# StereoscopicPi.net
KiCad netlist of a schematic drawn in Altium Designer
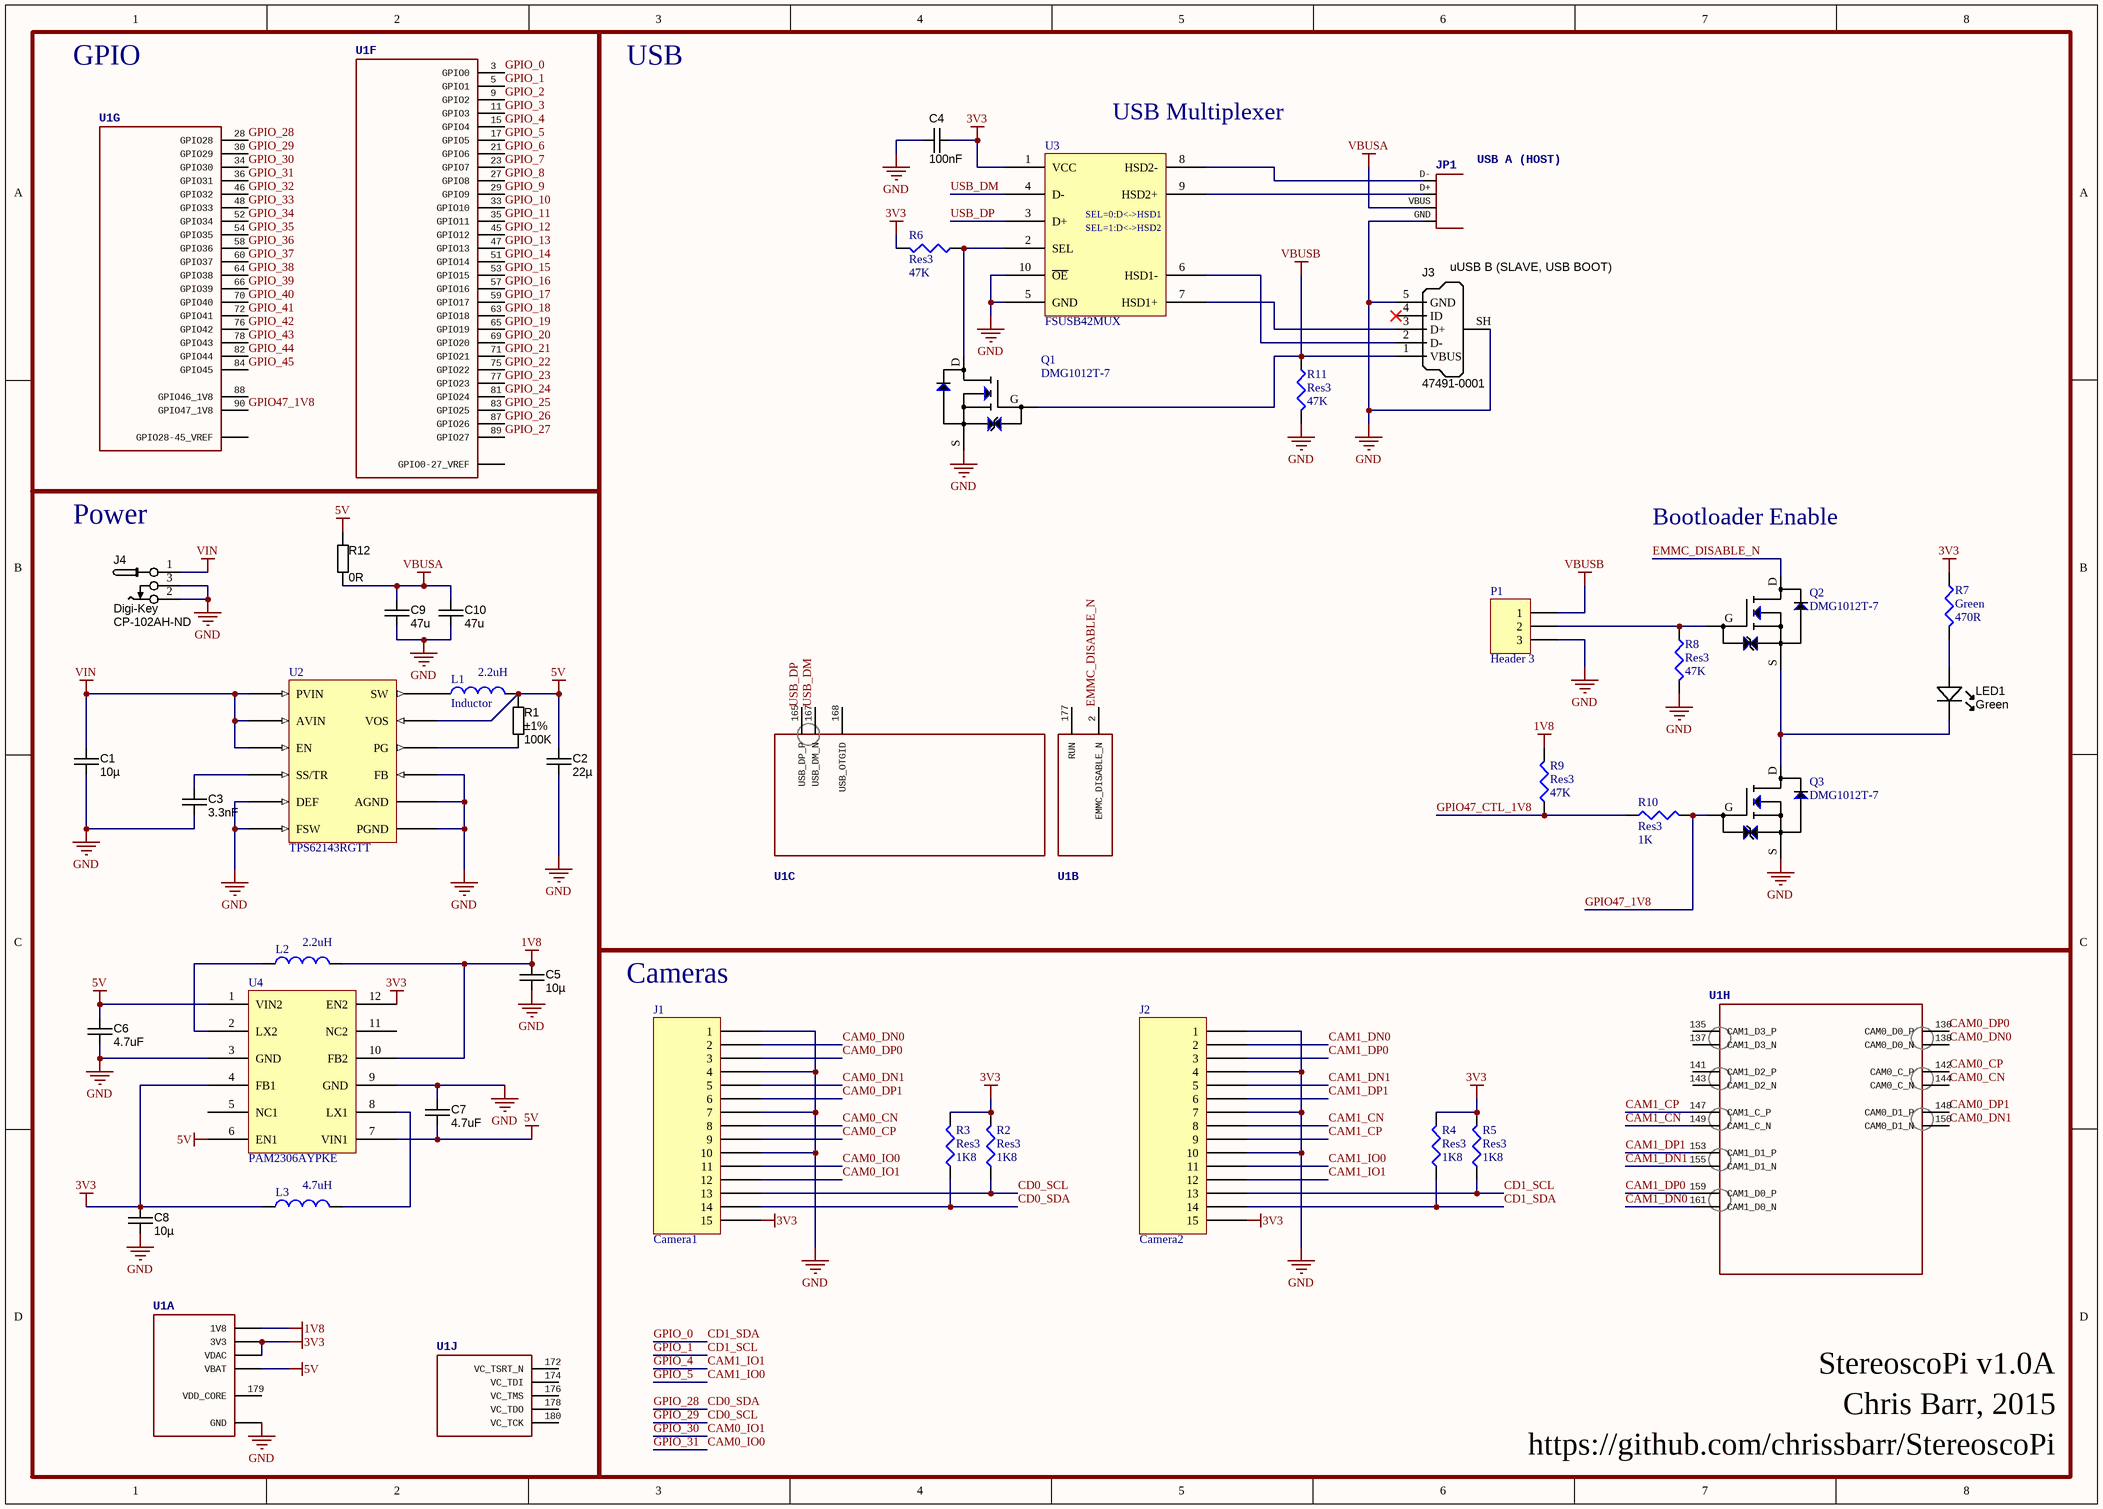
[diagram p0: StereoscopicPi.SchDoc]

(export (version "E")
  (design (tool "Eeschema 10.0.6"))
  (components
    (comp (ref "C1")
      (value "10µ")
      (footprint "CAPC3225X220N")
      (description "Capacitor SMD Cer 10uF 20% 16V X5R 1210")
      (fields (field (name "TOLERANCE") "±20%"))
      (libsource (lib "PBL - Capacitors") (part "CAPC_10u_1210_50V"))
    )
    (comp (ref "C2")
      (value "22µ")
      (footprint "CAPC3225X220N")
      (description "Capacitor SMD Cer 22uF 20% 6.3V X5R 1210")
      (fields (field (name "TOLERANCE") "±20%") (field (name "Comment") "approved sub OK"))
      (libsource (lib "PBL - Capacitors") (part "CAPC_22u_1210_6V3_X5R"))
    )
    (comp (ref "C3")
      (value "3.3nF")
      (footprint "CAPC1608X90N")
      (description "Capacitor SMD Cer 10nF 10% 50V X7R 0603")
      (fields (field (name "TOLERANCE") "±10%") (field (name "Comment") "Kemet C0603C332J3RACTU"))
      (libsource (lib "PBL - Capacitors") (part "CAPC_10n_0603_X7R_50V_10%"))
    )
    (comp (ref "C4")
      (value "100nF")
      (footprint "CAPC1608X90N")
      (description "Capacitor SMD Cer 10nF 10% 50V X7R 0603")
      (fields (field (name "TOLERANCE") "±10%"))
      (libsource (lib "PBL - Capacitors") (part "CAPC_10n_0603_X7R_50V_10%"))
    )
    (comp (ref "C5")
      (value "10µ")
      (footprint "CAPC3225X220N")
      (description "Capacitor SMD Cer 10uF 20% 16V X5R 1210")
      (fields (field (name "TOLERANCE") "±20%"))
      (libsource (lib "PBL - Capacitors") (part "CAPC_10u_1210_50V"))
    )
    (comp (ref "C6")
      (value "4.7uF")
      (footprint "CAPC2012X135N")
      (description "Capacitor SMD Cer 4.7uF 10% 16V X5R 0805")
      (fields (field (name "TOLERANCE") "±10%") (field (name "Comment") "approved sub OK"))
      (libsource (lib "PBL - Capacitors") (part "CAPC_4u7_0805"))
    )
    (comp (ref "C7")
      (value "4.7uF")
      (footprint "CAPC2012X135N")
      (description "Capacitor SMD Cer 4.7uF 10% 16V X5R 0805")
      (fields (field (name "TOLERANCE") "±10%") (field (name "Comment") "approved sub OK"))
      (libsource (lib "PBL - Capacitors") (part "CAPC_4u7_0805"))
    )
    (comp (ref "C8")
      (value "10µ")
      (footprint "CAPC3225X220N")
      (description "Capacitor SMD Cer 10uF 20% 16V X5R 1210")
      (fields (field (name "TOLERANCE") "±20%"))
      (libsource (lib "PBL - Capacitors") (part "CAPC_10u_1210_50V"))
    )
    (comp (ref "C9")
      (value "47u")
      (footprint "CAPC3225X220N")
      (description "Capacitor SMD Cer 47uF 10% 10V 1210")
      (fields (field (name "TOLERANCE") "±10%"))
      (libsource (lib "PBL - Capacitors") (part "CAPC_47u_1210_10V_X5R_10%"))
    )
    (comp (ref "C10")
      (value "47u")
      (footprint "CAPC3225X220N")
      (description "Capacitor SMD Cer 47uF 10% 10V 1210")
      (fields (field (name "TOLERANCE") "±10%"))
      (libsource (lib "PBL - Capacitors") (part "CAPC_47u_1210_10V_X5R_10%"))
    )
    (comp (ref "J1")
      (value "Camera1")
      (footprint "SFW15R-2STE1LF")
      (libsource (lib "Schlib1") (part "SFW15R-2STE1LF"))
    )
    (comp (ref "J2")
      (value "Camera2")
      (footprint "SFW15R-2STE1LF")
      (libsource (lib "Schlib1") (part "SFW15R-2STE1LF"))
    )
    (comp (ref "J3")
      (value "uUSB B (SLAVE, USB BOOT)")
      (footprint "USB_Micro-B_Molex_SMD")
      (description "Connector SMD USB Micro Type B middle mount")
      (fields (field (name "MANUFACTURER PART NUMBER 1") "47491-0001"))
      (libsource (lib "PBL - Connectors") (part "USB_Micro_TypeB"))
    )
    (comp (ref "J4")
      (value "CONN_PWR_JACK_2.1x5.5mm")
      (footprint "CONN_PWR_JACK_2.1x5.5mm")
      (description "Power Connector, THT, 2.1mm ID, 5.5mm OD")
      (fields (field (name "SUPPLIER 1") "Digi-Key") (field (name "SUPPLIER PART NUMBER 1") "CP-102AH-ND"))
      (libsource (lib "PBL - Connectors") (part "CONN_PWR_JACK_2.1x5.5mm"))
    )
    (comp (ref "JP1")
      (value "USB A (HOST)")
      (footprint "USB-A-S-NOSILK-FEMALE")
      (libsource (lib "SparkFun-Connectors") (part "USB-A-SMD"))
    )
    (comp (ref "L1")
      (value "Inductor")
      (footprint "IHLP-1212BZ-11")
      (fields (field (name "ALTIUM_VALUE") "2.2uH") (field (name "PUBLISHER") "Altium Limited"))
      (libsource (lib "Miscellaneous Devices") (part "Inductor"))
    )
    (comp (ref "L2")
      (value "2.2uH")
      (footprint "IHLP-1212BZ-11")
      (description "Inductor")
      (fields (field (name "Comment") "IHLP1212BZER2R2M11") (field (name "PUBLISHER") "Altium Limited"))
      (libsource (lib "Miscellaneous Devices") (part "Inductor"))
    )
    (comp (ref "L3")
      (value "4.7uH")
      (footprint "IHLP-2020CZ-11")
      (description "Inductor")
      (fields (field (name "Comment") "IHLP2020CZER4R7M11") (field (name "PUBLISHER") "Altium Limited"))
      (libsource (lib "Miscellaneous Devices") (part "Inductor"))
    )
    (comp (ref "LED1")
      (value "Green")
      (footprint "LED-0603-GREEN")
      (description "LED 0603 SMD Green 570nm 50mcd 20mA")
      (libsource (lib "PBL - Light Sources") (part "LED_SMD_Green_0603_570nm"))
    )
    (comp (ref "P1")
      (value "Header 3")
      (footprint "HDR1X3")
      (description "Header, 3-Pin")
      (fields (field (name "PUBLISHER") "Altium Limited"))
      (libsource (lib "Miscellaneous Connectors") (part "Header 3"))
    )
    (comp (ref "Q1")
      (value "DMG1012T-7")
      (footprint "DMG1012T-7")
      (libsource (lib "Schlib1") (part "DMG1012T-7"))
    )
    (comp (ref "Q2")
      (value "DMG1012T-7")
      (footprint "DMG1012T-7")
      (libsource (lib "Schlib1") (part "DMG1012T-7"))
    )
    (comp (ref "Q3")
      (value "DMG1012T-7")
      (footprint "DMG1012T-7")
      (libsource (lib "Schlib1") (part "DMG1012T-7"))
    )
    (comp (ref "R1")
      (value "100K")
      (footprint "RESC1608X55N")
      (description "Resistor SMD chip 100k Ohm 0.1W 1% 0603")
      (fields (field (name "TOLERANCE") "±1%") (field (name "Comment") "Thick Film"))
      (libsource (lib "PBL - Resistors") (part "RES_100K_0603_1%"))
    )
    (comp (ref "R2")
      (value "Res3")
      (footprint "J1-0603")
      (description "Resistor")
      (fields (field (name "ALTIUM_VALUE") "1K8") (field (name "PUBLISHER") "Altium Limited"))
      (libsource (lib "Miscellaneous Devices") (part "Res3"))
    )
    (comp (ref "R3")
      (value "Res3")
      (footprint "J1-0603")
      (description "Resistor")
      (fields (field (name "ALTIUM_VALUE") "1K8") (field (name "PUBLISHER") "Altium Limited"))
      (libsource (lib "Miscellaneous Devices") (part "Res3"))
    )
    (comp (ref "R4")
      (value "Res3")
      (footprint "J1-0603")
      (description "Resistor")
      (fields (field (name "ALTIUM_VALUE") "1K8") (field (name "PUBLISHER") "Altium Limited"))
      (libsource (lib "Miscellaneous Devices") (part "Res3"))
    )
    (comp (ref "R5")
      (value "Res3")
      (footprint "J1-0603")
      (description "Resistor")
      (fields (field (name "ALTIUM_VALUE") "1K8") (field (name "PUBLISHER") "Altium Limited"))
      (libsource (lib "Miscellaneous Devices") (part "Res3"))
    )
    (comp (ref "R6")
      (value "Res3")
      (footprint "J1-0603")
      (description "Resistor")
      (fields (field (name "ALTIUM_VALUE") "47K") (field (name "PUBLISHER") "Altium Limited"))
      (libsource (lib "Miscellaneous Devices") (part "Res3"))
    )
    (comp (ref "R7")
      (value "Green")
      (footprint "J1-0603")
      (description "Resistor")
      (fields (field (name "ALTIUM_VALUE") "470R") (field (name "PUBLISHER") "Altium Limited"))
      (libsource (lib "Miscellaneous Devices") (part "Res3"))
    )
    (comp (ref "R8")
      (value "Res3")
      (footprint "J1-0603")
      (description "Resistor")
      (fields (field (name "ALTIUM_VALUE") "47K") (field (name "PUBLISHER") "Altium Limited"))
      (libsource (lib "Miscellaneous Devices") (part "Res3"))
    )
    (comp (ref "R9")
      (value "Res3")
      (footprint "J1-0603")
      (description "Resistor")
      (fields (field (name "ALTIUM_VALUE") "47K") (field (name "PUBLISHER") "Altium Limited"))
      (libsource (lib "Miscellaneous Devices") (part "Res3"))
    )
    (comp (ref "R10")
      (value "Res3")
      (footprint "J1-0603")
      (description "Resistor")
      (fields (field (name "ALTIUM_VALUE") "1K") (field (name "PUBLISHER") "Altium Limited"))
      (libsource (lib "Miscellaneous Devices") (part "Res3"))
    )
    (comp (ref "R11")
      (value "Res3")
      (footprint "J1-0603")
      (description "Resistor")
      (fields (field (name "ALTIUM_VALUE") "47K") (field (name "PUBLISHER") "Altium Limited"))
      (libsource (lib "Miscellaneous Devices") (part "Res3"))
    )
    (comp (ref "R12")
      (value "0R")
      (footprint "RESC1608X55N")
      (description "Resistor SMD chip 100k Ohm 0.1W 1% 0603")
      (fields (field (name "TOLERANCE") "±1%") (field (name "Comment") "Thick Film"))
      (libsource (lib "PBL - Resistors") (part "RES_100K_0603_1%"))
    )
    (comp (ref "U1")
      (value "Raspberry Pi Compute Module As anounced in this blog post  http://www.raspberrypi.org/raspberry-pi-compute-module-new-product/  Based on infomation from this schematic http://www.raspberrypi.org/wp-content/uploads/2014/04/RPI-CM-V1_1-SCHEMATIC.pdf  Footprint is unproven and no matching part confimed as of yet")
      (footprint "1-1376408-4")
      (libsource (lib "Ciseco Pi Compute Module") (part "RASPBERRY_PI_CM-1-1376408-4"))
    )
    (comp (ref "U2")
      (value "TPS62143RGTT")
      (footprint "QFN50P300X300X100_HS-17M")
      (libsource (lib "Schlib1") (part "TPS62143 5V 2A LDO SMPS Buck"))
    )
    (comp (ref "U3")
      (value "FSUSB42MUX")
      (footprint "FSUSB42MUX")
      (libsource (lib "Schlib1") (part "FSUSB42MUX"))
    )
    (comp (ref "U4")
      (value "PAM2306AYPKE")
      (footprint "PAM2306")
      (libsource (lib "Schlib1") (part "PAM2306"))
    )
  )
  (nets
    (net (code "1") (name "/CAM0_CN") (class "Default")
      (node (ref "J1") (pin "8") (pinfunction "8_8") (pintype "passive"))
      (node (ref "U1") (pin "144") (pinfunction "CAM0_C_N_144") (pintype "passive"))
    )
    (net (code "2") (name "/CAM0_CP") (class "Default")
      (node (ref "J1") (pin "9") (pinfunction "9_9") (pintype "passive"))
      (node (ref "U1") (pin "142") (pinfunction "CAM0_C_P_142") (pintype "passive"))
    )
    (net (code "3") (name "/CAM0_DN0") (class "Default")
      (node (ref "J1") (pin "2") (pinfunction "2_2") (pintype "passive"))
      (node (ref "U1") (pin "138") (pinfunction "CAM0_D0_N_138") (pintype "passive"))
    )
    (net (code "4") (name "/CAM0_DN1") (class "Default")
      (node (ref "J1") (pin "5") (pinfunction "5_5") (pintype "passive"))
      (node (ref "U1") (pin "150") (pinfunction "CAM0_D1_N_150") (pintype "passive"))
    )
    (net (code "5") (name "/CAM0_DP0") (class "Default")
      (node (ref "J1") (pin "3") (pinfunction "3_3") (pintype "passive"))
      (node (ref "U1") (pin "136") (pinfunction "CAM0_D0_P_136") (pintype "passive"))
    )
    (net (code "6") (name "/CAM0_DP1") (class "Default")
      (node (ref "J1") (pin "6") (pinfunction "6_6") (pintype "passive"))
      (node (ref "U1") (pin "148") (pinfunction "CAM0_D1_P_148") (pintype "passive"))
    )
    (net (code "7") (name "/CAM0_IO0") (class "Default")
      (node (ref "J1") (pin "11") (pinfunction "11_11") (pintype "passive"))
      (node (ref "U1") (pin "36") (pinfunction "GPIO31_36") (pintype "passive"))
    )
    (net (code "8") (name "/CAM0_IO1") (class "Default")
      (node (ref "J1") (pin "12") (pinfunction "12_12") (pintype "passive"))
      (node (ref "U1") (pin "34") (pinfunction "GPIO30_34") (pintype "passive"))
    )
    (net (code "9") (name "/CAM1_CN") (class "Default")
      (node (ref "J2") (pin "8") (pinfunction "8_8") (pintype "passive"))
      (node (ref "U1") (pin "149") (pinfunction "CAM1_C_N_149") (pintype "passive"))
    )
    (net (code "10") (name "/CAM1_CP") (class "Default")
      (node (ref "J2") (pin "9") (pinfunction "9_9") (pintype "passive"))
      (node (ref "U1") (pin "147") (pinfunction "CAM1_C_P_147") (pintype "passive"))
    )
    (net (code "11") (name "/CAM1_DN0") (class "Default")
      (node (ref "J2") (pin "2") (pinfunction "2_2") (pintype "passive"))
      (node (ref "U1") (pin "161") (pinfunction "CAM1_D0_N_161") (pintype "passive"))
    )
    (net (code "12") (name "/CAM1_DN1") (class "Default")
      (node (ref "J2") (pin "5") (pinfunction "5_5") (pintype "passive"))
      (node (ref "U1") (pin "155") (pinfunction "CAM1_D1_N_155") (pintype "passive"))
    )
    (net (code "13") (name "/CAM1_DP0") (class "Default")
      (node (ref "J2") (pin "3") (pinfunction "3_3") (pintype "passive"))
      (node (ref "U1") (pin "159") (pinfunction "CAM1_D0_P_159") (pintype "passive"))
    )
    (net (code "14") (name "/CAM1_DP1") (class "Default")
      (node (ref "J2") (pin "6") (pinfunction "6_6") (pintype "passive"))
      (node (ref "U1") (pin "153") (pinfunction "CAM1_D1_P_153") (pintype "passive"))
    )
    (net (code "15") (name "/CAM1_IO0") (class "Default")
      (node (ref "J2") (pin "11") (pinfunction "11_11") (pintype "passive"))
      (node (ref "U1") (pin "17") (pinfunction "GPIO5_17") (pintype "passive"))
    )
    (net (code "16") (name "/CAM1_IO1") (class "Default")
      (node (ref "J2") (pin "12") (pinfunction "12_12") (pintype "passive"))
      (node (ref "U1") (pin "15") (pinfunction "GPIO4_15") (pintype "passive"))
    )
    (net (code "17") (name "/CD0_SCL") (class "Default")
      (node (ref "J1") (pin "13") (pinfunction "13_13") (pintype "passive"))
      (node (ref "R2") (pin "1") (pinfunction "1_1") (pintype "passive"))
      (node (ref "U1") (pin "30") (pinfunction "GPIO29_30") (pintype "passive"))
    )
    (net (code "18") (name "/CD0_SDA") (class "Default")
      (node (ref "J1") (pin "14") (pinfunction "14_14") (pintype "passive"))
      (node (ref "R3") (pin "1") (pinfunction "1_1") (pintype "passive"))
      (node (ref "U1") (pin "28") (pinfunction "GPIO28_28") (pintype "passive"))
    )
    (net (code "19") (name "/CD1_SCL") (class "Default")
      (node (ref "J2") (pin "13") (pinfunction "13_13") (pintype "passive"))
      (node (ref "R5") (pin "1") (pinfunction "1_1") (pintype "passive"))
      (node (ref "U1") (pin "5") (pinfunction "GPIO1_5") (pintype "passive"))
    )
    (net (code "20") (name "/CD1_SDA") (class "Default")
      (node (ref "J2") (pin "14") (pinfunction "14_14") (pintype "passive"))
      (node (ref "R4") (pin "1") (pinfunction "1_1") (pintype "passive"))
      (node (ref "U1") (pin "3") (pinfunction "GPIO0_3") (pintype "passive"))
    )
    (net (code "21") (name "/EMMC_DISABLE_N") (class "Default")
      (node (ref "Q2") (pin "D") (pinfunction "D_D") (pintype "passive"))
      (node (ref "U1") (pin "2") (pinfunction "EMMC_DISABLE_N_2") (pintype "passive"))
    )
    (net (code "22") (name "/GPIO47_1V8") (class "Default")
      (node (ref "Q3") (pin "G") (pinfunction "G_G") (pintype "passive"))
      (node (ref "R10") (pin "2") (pinfunction "2_2") (pintype "passive"))
      (node (ref "U1") (pin "90") (pinfunction "GPIO47_1V8_90") (pintype "passive"))
    )
    (net (code "23") (name "/GPIO47_CTL_1V8") (class "Default")
      (node (ref "R10") (pin "1") (pinfunction "1_1") (pintype "passive"))
      (node (ref "R9") (pin "1") (pinfunction "1_1") (pintype "passive"))
    )
    (net (code "24") (name "/GPIO_2") (class "Default")
      (node (ref "U1") (pin "9") (pinfunction "GPIO2_9") (pintype "passive"))
    )
    (net (code "25") (name "/GPIO_3") (class "Default")
      (node (ref "U1") (pin "11") (pinfunction "GPIO3_11") (pintype "passive"))
    )
    (net (code "26") (name "/GPIO_6") (class "Default")
      (node (ref "U1") (pin "21") (pinfunction "GPIO6_21") (pintype "passive"))
    )
    (net (code "27") (name "/GPIO_7") (class "Default")
      (node (ref "U1") (pin "23") (pinfunction "GPIO7_23") (pintype "passive"))
    )
    (net (code "28") (name "/GPIO_8") (class "Default")
      (node (ref "U1") (pin "27") (pinfunction "GPIO8_27") (pintype "passive"))
    )
    (net (code "29") (name "/GPIO_9") (class "Default")
      (node (ref "U1") (pin "29") (pinfunction "GPIO9_29") (pintype "passive"))
    )
    (net (code "30") (name "/GPIO_10") (class "Default")
      (node (ref "U1") (pin "33") (pinfunction "GPIO10_33") (pintype "passive"))
    )
    (net (code "31") (name "/GPIO_11") (class "Default")
      (node (ref "U1") (pin "35") (pinfunction "GPIO11_35") (pintype "passive"))
    )
    (net (code "32") (name "/GPIO_12") (class "Default")
      (node (ref "U1") (pin "45") (pinfunction "GPIO12_45") (pintype "passive"))
    )
    (net (code "33") (name "/GPIO_13") (class "Default")
      (node (ref "U1") (pin "47") (pinfunction "GPIO13_47") (pintype "passive"))
    )
    (net (code "34") (name "/GPIO_14") (class "Default")
      (node (ref "U1") (pin "51") (pinfunction "GPIO14_51") (pintype "passive"))
    )
    (net (code "35") (name "/GPIO_15") (class "Default")
      (node (ref "U1") (pin "53") (pinfunction "GPIO15_53") (pintype "passive"))
    )
    (net (code "36") (name "/GPIO_16") (class "Default")
      (node (ref "U1") (pin "57") (pinfunction "GPIO16_57") (pintype "passive"))
    )
    (net (code "37") (name "/GPIO_17") (class "Default")
      (node (ref "U1") (pin "59") (pinfunction "GPIO17_59") (pintype "passive"))
    )
    (net (code "38") (name "/GPIO_18") (class "Default")
      (node (ref "U1") (pin "63") (pinfunction "GPIO18_63") (pintype "passive"))
    )
    (net (code "39") (name "/GPIO_19") (class "Default")
      (node (ref "U1") (pin "65") (pinfunction "GPIO19_65") (pintype "passive"))
    )
    (net (code "40") (name "/GPIO_20") (class "Default")
      (node (ref "U1") (pin "69") (pinfunction "GPIO20_69") (pintype "passive"))
    )
    (net (code "41") (name "/GPIO_21") (class "Default")
      (node (ref "U1") (pin "71") (pinfunction "GPIO21_71") (pintype "passive"))
    )
    (net (code "42") (name "/GPIO_22") (class "Default")
      (node (ref "U1") (pin "75") (pinfunction "GPIO22_75") (pintype "passive"))
    )
    (net (code "43") (name "/GPIO_23") (class "Default")
      (node (ref "U1") (pin "77") (pinfunction "GPIO23_77") (pintype "passive"))
    )
    (net (code "44") (name "/GPIO_24") (class "Default")
      (node (ref "U1") (pin "81") (pinfunction "GPIO24_81") (pintype "passive"))
    )
    (net (code "45") (name "/GPIO_25") (class "Default")
      (node (ref "U1") (pin "83") (pinfunction "GPIO25_83") (pintype "passive"))
    )
    (net (code "46") (name "/GPIO_26") (class "Default")
      (node (ref "U1") (pin "87") (pinfunction "GPIO26_87") (pintype "passive"))
    )
    (net (code "47") (name "/GPIO_27") (class "Default")
      (node (ref "U1") (pin "89") (pinfunction "GPIO27_89") (pintype "passive"))
    )
    (net (code "48") (name "/GPIO_32") (class "Default")
      (node (ref "U1") (pin "46") (pinfunction "GPIO32_46") (pintype "passive"))
    )
    (net (code "49") (name "/GPIO_33") (class "Default")
      (node (ref "U1") (pin "48") (pinfunction "GPIO33_48") (pintype "passive"))
    )
    (net (code "50") (name "/GPIO_34") (class "Default")
      (node (ref "U1") (pin "52") (pinfunction "GPIO34_52") (pintype "passive"))
    )
    (net (code "51") (name "/GPIO_35") (class "Default")
      (node (ref "U1") (pin "54") (pinfunction "GPIO35_54") (pintype "passive"))
    )
    (net (code "52") (name "/GPIO_36") (class "Default")
      (node (ref "U1") (pin "58") (pinfunction "GPIO36_58") (pintype "passive"))
    )
    (net (code "53") (name "/GPIO_37") (class "Default")
      (node (ref "U1") (pin "60") (pinfunction "GPIO37_60") (pintype "passive"))
    )
    (net (code "54") (name "/GPIO_38") (class "Default")
      (node (ref "U1") (pin "64") (pinfunction "GPIO38_64") (pintype "passive"))
    )
    (net (code "55") (name "/GPIO_39") (class "Default")
      (node (ref "U1") (pin "66") (pinfunction "GPIO39_66") (pintype "passive"))
    )
    (net (code "56") (name "/GPIO_40") (class "Default")
      (node (ref "U1") (pin "70") (pinfunction "GPIO40_70") (pintype "passive"))
    )
    (net (code "57") (name "/GPIO_41") (class "Default")
      (node (ref "U1") (pin "72") (pinfunction "GPIO41_72") (pintype "passive"))
    )
    (net (code "58") (name "/GPIO_42") (class "Default")
      (node (ref "U1") (pin "76") (pinfunction "GPIO42_76") (pintype "passive"))
    )
    (net (code "59") (name "/GPIO_43") (class "Default")
      (node (ref "U1") (pin "78") (pinfunction "GPIO43_78") (pintype "passive"))
    )
    (net (code "60") (name "/GPIO_44") (class "Default")
      (node (ref "U1") (pin "82") (pinfunction "GPIO44_82") (pintype "passive"))
    )
    (net (code "61") (name "/GPIO_45") (class "Default")
      (node (ref "U1") (pin "84") (pinfunction "GPIO45_84") (pintype "passive"))
    )
    (net (code "62") (name "/USB_DM") (class "Default")
      (node (ref "U1") (pin "167") (pinfunction "USB_DM_N_167") (pintype "passive"))
      (node (ref "U3") (pin "4") (pinfunction "D-_4") (pintype "passive"))
    )
    (net (code "63") (name "/USB_DP") (class "Default")
      (node (ref "U1") (pin "165") (pinfunction "USB_DP_P_165") (pintype "passive"))
      (node (ref "U3") (pin "3") (pinfunction "D+_3") (pintype "passive"))
    )
    (net (code "64") (name "1V8") (class "Default")
      (node (ref "C5") (pin "1") (pintype "passive"))
      (node (ref "L2") (pin "1") (pinfunction "2_1") (pintype "passive"))
      (node (ref "R9") (pin "2") (pinfunction "2_2") (pintype "passive"))
      (node (ref "U1") (pin "1V8") (pinfunction "1V8_1V8") (pintype "passive"))
      (node (ref "U4") (pin "10") (pinfunction "FB2_10") (pintype "passive"))
    )
    (net (code "65") (name "3V3") (class "Default")
      (node (ref "C4") (pin "2") (pintype "passive"))
      (node (ref "C8") (pin "1") (pintype "passive"))
      (node (ref "J1") (pin "15") (pinfunction "15_15") (pintype "passive"))
      (node (ref "J2") (pin "15") (pinfunction "15_15") (pintype "passive"))
      (node (ref "L3") (pin "0") (pinfunction "1_0") (pintype "passive"))
      (node (ref "R2") (pin "2") (pinfunction "2_2") (pintype "passive"))
      (node (ref "R3") (pin "2") (pinfunction "2_2") (pintype "passive"))
      (node (ref "R4") (pin "2") (pinfunction "2_2") (pintype "passive"))
      (node (ref "R5") (pin "2") (pinfunction "2_2") (pintype "passive"))
      (node (ref "R6") (pin "2") (pinfunction "2_2") (pintype "passive"))
      (node (ref "R7") (pin "1") (pinfunction "1_1") (pintype "passive"))
      (node (ref "U1") (pin "3V3") (pinfunction "3V3_3V3") (pintype "passive"))
      (node (ref "U1") (pin "VDAC") (pinfunction "VDAC_VDAC") (pintype "passive"))
      (node (ref "U3") (pin "1") (pinfunction "VCC_1") (pintype "passive"))
      (node (ref "U4") (pin "12") (pinfunction "EN2_12") (pintype "passive"))
      (node (ref "U4") (pin "4") (pinfunction "FB1_4") (pintype "passive"))
    )
    (net (code "66") (name "5V") (class "Default")
      (node (ref "C2") (pin "1") (pintype "passive"))
      (node (ref "C6") (pin "1") (pintype "passive"))
      (node (ref "C7") (pin "2") (pintype "passive"))
      (node (ref "L1") (pin "1") (pinfunction "2_1") (pintype "passive"))
      (node (ref "R1") (pin "1") (pinfunction "1_1") (pintype "passive"))
      (node (ref "R12") (pin "1") (pinfunction "1_1") (pintype "passive"))
      (node (ref "U1") (pin "VBAT") (pinfunction "VBAT_VBAT") (pintype "passive"))
      (node (ref "U2") (pin "14") (pinfunction "VOS_14") (pintype "input"))
      (node (ref "U4") (pin "1") (pinfunction "VIN2_1") (pintype "passive"))
      (node (ref "U4") (pin "6") (pinfunction "EN1_6") (pintype "passive"))
      (node (ref "U4") (pin "7") (pinfunction "VIN1_7") (pintype "passive"))
    )
    (net (code "67") (name "GND") (class "Default")
      (node (ref "C1") (pin "2") (pintype "passive"))
      (node (ref "C10") (pin "2") (pintype "passive"))
      (node (ref "C2") (pin "2") (pintype "passive"))
      (node (ref "C3") (pin "2") (pintype "passive"))
      (node (ref "C4") (pin "1") (pintype "passive"))
      (node (ref "C5") (pin "2") (pintype "passive"))
      (node (ref "C6") (pin "2") (pintype "passive"))
      (node (ref "C7") (pin "1") (pintype "passive"))
      (node (ref "C8") (pin "2") (pintype "passive"))
      (node (ref "C9") (pin "2") (pintype "passive"))
      (node (ref "J1") (pin "1") (pinfunction "1_1") (pintype "passive"))
      (node (ref "J1") (pin "10") (pinfunction "10_10") (pintype "passive"))
      (node (ref "J1") (pin "4") (pinfunction "4_4") (pintype "passive"))
      (node (ref "J1") (pin "7") (pinfunction "7_7") (pintype "passive"))
      (node (ref "J2") (pin "1") (pinfunction "1_1") (pintype "passive"))
      (node (ref "J2") (pin "10") (pinfunction "10_10") (pintype "passive"))
      (node (ref "J2") (pin "4") (pinfunction "4_4") (pintype "passive"))
      (node (ref "J2") (pin "7") (pinfunction "7_7") (pintype "passive"))
      (node (ref "J3") (pin "5") (pinfunction "GND_5") (pintype "passive"))
      (node (ref "J3") (pin "SH") (pinfunction "Shell_SH") (pintype "passive"))
      (node (ref "J4") (pin "2") (pinfunction "2_2") (pintype "passive"))
      (node (ref "J4") (pin "3") (pinfunction "3_3") (pintype "passive"))
      (node (ref "JP1") (pin "GND") (pinfunction "GND_GND") (pintype "passive"))
      (node (ref "P1") (pin "3") (pinfunction "3_3") (pintype "passive"))
      (node (ref "Q1") (pin "S") (pinfunction "3_S") (pintype "passive"))
      (node (ref "Q3") (pin "S") (pinfunction "3_S") (pintype "passive"))
      (node (ref "R11") (pin "2") (pinfunction "2_2") (pintype "passive"))
      (node (ref "R8") (pin "2") (pinfunction "2_2") (pintype "passive"))
      (node (ref "U1") (pin "GND") (pinfunction "GND_GND") (pintype "passive"))
      (node (ref "U2") (pin "15") (pinfunction "PGND_15") (pintype "passive"))
      (node (ref "U2") (pin "5") (pinfunction "FB_5") (pintype "input"))
      (node (ref "U2") (pin "6") (pinfunction "AGND_6") (pintype "passive"))
      (node (ref "U2") (pin "7") (pinfunction "FSW_7") (pintype "input"))
      (node (ref "U2") (pin "8") (pinfunction "DEF_8") (pintype "input"))
      (node (ref "U3") (pin "10") (pinfunction "~{OE}_10") (pintype "passive"))
      (node (ref "U3") (pin "5") (pinfunction "GND_5") (pintype "passive"))
      (node (ref "U4") (pin "3") (pinfunction "GND_3") (pintype "passive"))
      (node (ref "U4") (pin "9") (pinfunction "GND_9") (pintype "passive"))
    )
    (net (code "68") (name "Net-(J3-D+)") (class "Default")
      (node (ref "J3") (pin "3") (pinfunction "D+_3") (pintype "passive"))
      (node (ref "U3") (pin "7") (pinfunction "HSD1+_7") (pintype "passive"))
    )
    (net (code "69") (name "Net-(J3-D-)") (class "Default")
      (node (ref "J3") (pin "2") (pinfunction "D-_2") (pintype "passive"))
      (node (ref "U3") (pin "6") (pinfunction "HSD1-_6") (pintype "passive"))
    )
    (net (code "70") (name "Net-(L1-1)") (class "Default")
      (node (ref "L1") (pin "0") (pinfunction "1_0") (pintype "passive"))
      (node (ref "U2") (pin "1") (pinfunction "SW_1") (pintype "output"))
    )
    (net (code "71") (name "Net-(L2-1)") (class "Default")
      (node (ref "L2") (pin "0") (pinfunction "1_0") (pintype "passive"))
      (node (ref "U4") (pin "2") (pinfunction "LX2_2") (pintype "passive"))
    )
    (net (code "72") (name "Net-(L3-2)") (class "Default")
      (node (ref "L3") (pin "1") (pinfunction "2_1") (pintype "passive"))
      (node (ref "U4") (pin "8") (pinfunction "LX1_8") (pintype "passive"))
    )
    (net (code "73") (name "Net-(LED1-PadA)") (class "Default")
      (node (ref "LED1") (pin "A") (pinfunction "A_A") (pintype "passive"))
      (node (ref "R7") (pin "2") (pinfunction "2_2") (pintype "passive"))
    )
    (net (code "74") (name "Net-(P1-Pad2)") (class "Default")
      (node (ref "P1") (pin "2") (pinfunction "2_2") (pintype "passive"))
      (node (ref "Q2") (pin "G") (pinfunction "G_G") (pintype "passive"))
      (node (ref "R8") (pin "1") (pinfunction "1_1") (pintype "passive"))
    )
    (net (code "75") (name "Net-(Q2-3)") (class "Default")
      (node (ref "LED1") (pin "K") (pinfunction "K_K") (pintype "passive"))
      (node (ref "Q2") (pin "S") (pinfunction "3_S") (pintype "passive"))
      (node (ref "Q3") (pin "D") (pinfunction "D_D") (pintype "passive"))
    )
    (net (code "76") (name "Net-(U2-PG)") (class "Default")
      (node (ref "R1") (pin "2") (pinfunction "2_2") (pintype "passive"))
      (node (ref "U2") (pin "4") (pinfunction "PG_4") (pintype "output"))
    )
    (net (code "77") (name "Net-(U2-SS{slash}TR)") (class "Default")
      (node (ref "C3") (pin "1") (pintype "passive"))
      (node (ref "U2") (pin "9") (pinfunction "SS/TR_9") (pintype "input"))
    )
    (net (code "78") (name "Net-(U3-HSD2+)") (class "Default")
      (node (ref "JP1") (pin "D+") (pinfunction "D+_D+") (pintype "passive"))
      (node (ref "U3") (pin "9") (pinfunction "HSD2+_9") (pintype "passive"))
    )
    (net (code "79") (name "Net-(U3-HSD2-)") (class "Default")
      (node (ref "JP1") (pin "D-") (pinfunction "D-_D-") (pintype "passive"))
      (node (ref "U3") (pin "8") (pinfunction "HSD2-_8") (pintype "passive"))
    )
    (net (code "80") (name "Net-(U3-SEL)") (class "Default")
      (node (ref "Q1") (pin "D") (pinfunction "D_D") (pintype "passive"))
      (node (ref "R6") (pin "1") (pinfunction "1_1") (pintype "passive"))
      (node (ref "U3") (pin "2") (pinfunction "SEL_2") (pintype "passive"))
    )
    (net (code "81") (name "VBUSA") (class "Default")
      (node (ref "C10") (pin "1") (pintype "passive"))
      (node (ref "C9") (pin "1") (pintype "passive"))
      (node (ref "JP1") (pin "VBUS") (pinfunction "VBUS_VBUS") (pintype "passive"))
      (node (ref "R12") (pin "2") (pinfunction "2_2") (pintype "passive"))
    )
    (net (code "82") (name "VBUSB") (class "Default")
      (node (ref "J3") (pin "1") (pinfunction "VBUS_1") (pintype "passive"))
      (node (ref "P1") (pin "1") (pinfunction "1_1") (pintype "passive"))
      (node (ref "Q1") (pin "G") (pinfunction "G_G") (pintype "passive"))
      (node (ref "R11") (pin "1") (pinfunction "1_1") (pintype "passive"))
    )
    (net (code "83") (name "VIN") (class "Default")
      (node (ref "C1") (pin "1") (pintype "passive"))
      (node (ref "J4") (pin "1") (pinfunction "1_1") (pintype "passive"))
      (node (ref "U2") (pin "10") (pinfunction "AVIN_10") (pintype "input"))
      (node (ref "U2") (pin "11") (pinfunction "PVIN_11") (pintype "input"))
      (node (ref "U2") (pin "13") (pinfunction "EN_13") (pintype "input"))
    )
    (net (code "84") (name "unconnected-(J3-ID-Pad4)") (class "Default")
      (node (ref "J3") (pin "4") (pinfunction "ID_4") (pintype "passive+no_connect"))
    )
    (net (code "85") (name "unconnected-(U1A-VDD_CORE-Pad179)") (class "Default")
      (node (ref "U1") (pin "179") (pinfunction "VDD_CORE_179") (pintype "passive"))
    )
    (net (code "86") (name "unconnected-(U1B-RUN-Pad177)") (class "Default")
      (node (ref "U1") (pin "177") (pinfunction "RUN_177") (pintype "passive"))
    )
    (net (code "87") (name "unconnected-(U1C-USB_OTGID-Pad168)") (class "Default")
      (node (ref "U1") (pin "168") (pinfunction "USB_OTGID_168") (pintype "passive"))
    )
    (net (code "88") (name "unconnected-(U1F-GPIO0-27_VREF-Pad39_40)") (class "Default")
      (node (ref "U1") (pin "39_40") (pinfunction "GPIO0-27_VREF_39_40") (pintype "passive"))
    )
    (net (code "89") (name "unconnected-(U1G-GPIO28-45_VREF-Pad41_42)") (class "Default")
      (node (ref "U1") (pin "41_42") (pinfunction "GPIO28-45_VREF_41_42") (pintype "passive"))
    )
    (net (code "90") (name "unconnected-(U1G-GPIO46_1V8-Pad88)") (class "Default")
      (node (ref "U1") (pin "88") (pinfunction "GPIO46_1V8_88") (pintype "passive"))
    )
    (net (code "91") (name "unconnected-(U1H-CAM1_D2_N-Pad143)") (class "Default")
      (node (ref "U1") (pin "143") (pinfunction "CAM1_D2_N_143") (pintype "passive"))
    )
    (net (code "92") (name "unconnected-(U1H-CAM1_D2_P-Pad141)") (class "Default")
      (node (ref "U1") (pin "141") (pinfunction "CAM1_D2_P_141") (pintype "passive"))
    )
    (net (code "93") (name "unconnected-(U1H-CAM1_D3_N-Pad137)") (class "Default")
      (node (ref "U1") (pin "137") (pinfunction "CAM1_D3_N_137") (pintype "passive"))
    )
    (net (code "94") (name "unconnected-(U1H-CAM1_D3_P-Pad135)") (class "Default")
      (node (ref "U1") (pin "135") (pinfunction "CAM1_D3_P_135") (pintype "passive"))
    )
    (net (code "95") (name "unconnected-(U1J-VC_TCK-Pad180)") (class "Default")
      (node (ref "U1") (pin "180") (pinfunction "VC_TCK_180") (pintype "passive"))
    )
    (net (code "96") (name "unconnected-(U1J-VC_TDI-Pad174)") (class "Default")
      (node (ref "U1") (pin "174") (pinfunction "VC_TDI_174") (pintype "passive"))
    )
    (net (code "97") (name "unconnected-(U1J-VC_TDO-Pad178)") (class "Default")
      (node (ref "U1") (pin "178") (pinfunction "VC_TDO_178") (pintype "passive"))
    )
    (net (code "98") (name "unconnected-(U1J-VC_TMS-Pad176)") (class "Default")
      (node (ref "U1") (pin "176") (pinfunction "VC_TMS_176") (pintype "passive"))
    )
    (net (code "99") (name "unconnected-(U1J-VC_TSRT_N-Pad172)") (class "Default")
      (node (ref "U1") (pin "172") (pinfunction "VC_TSRT_N_172") (pintype "passive"))
    )
    (net (code "100") (name "unconnected-(U4-NC1-Pad5)") (class "Default")
      (node (ref "U4") (pin "5") (pinfunction "NC1_5") (pintype "passive"))
    )
    (net (code "101") (name "unconnected-(U4-NC2-Pad11)") (class "Default")
      (node (ref "U4") (pin "11") (pinfunction "NC2_11") (pintype "passive"))
    )
  )
)
